# Supplies.net
KiCad netlist of a schematic drawn in Altium Designer
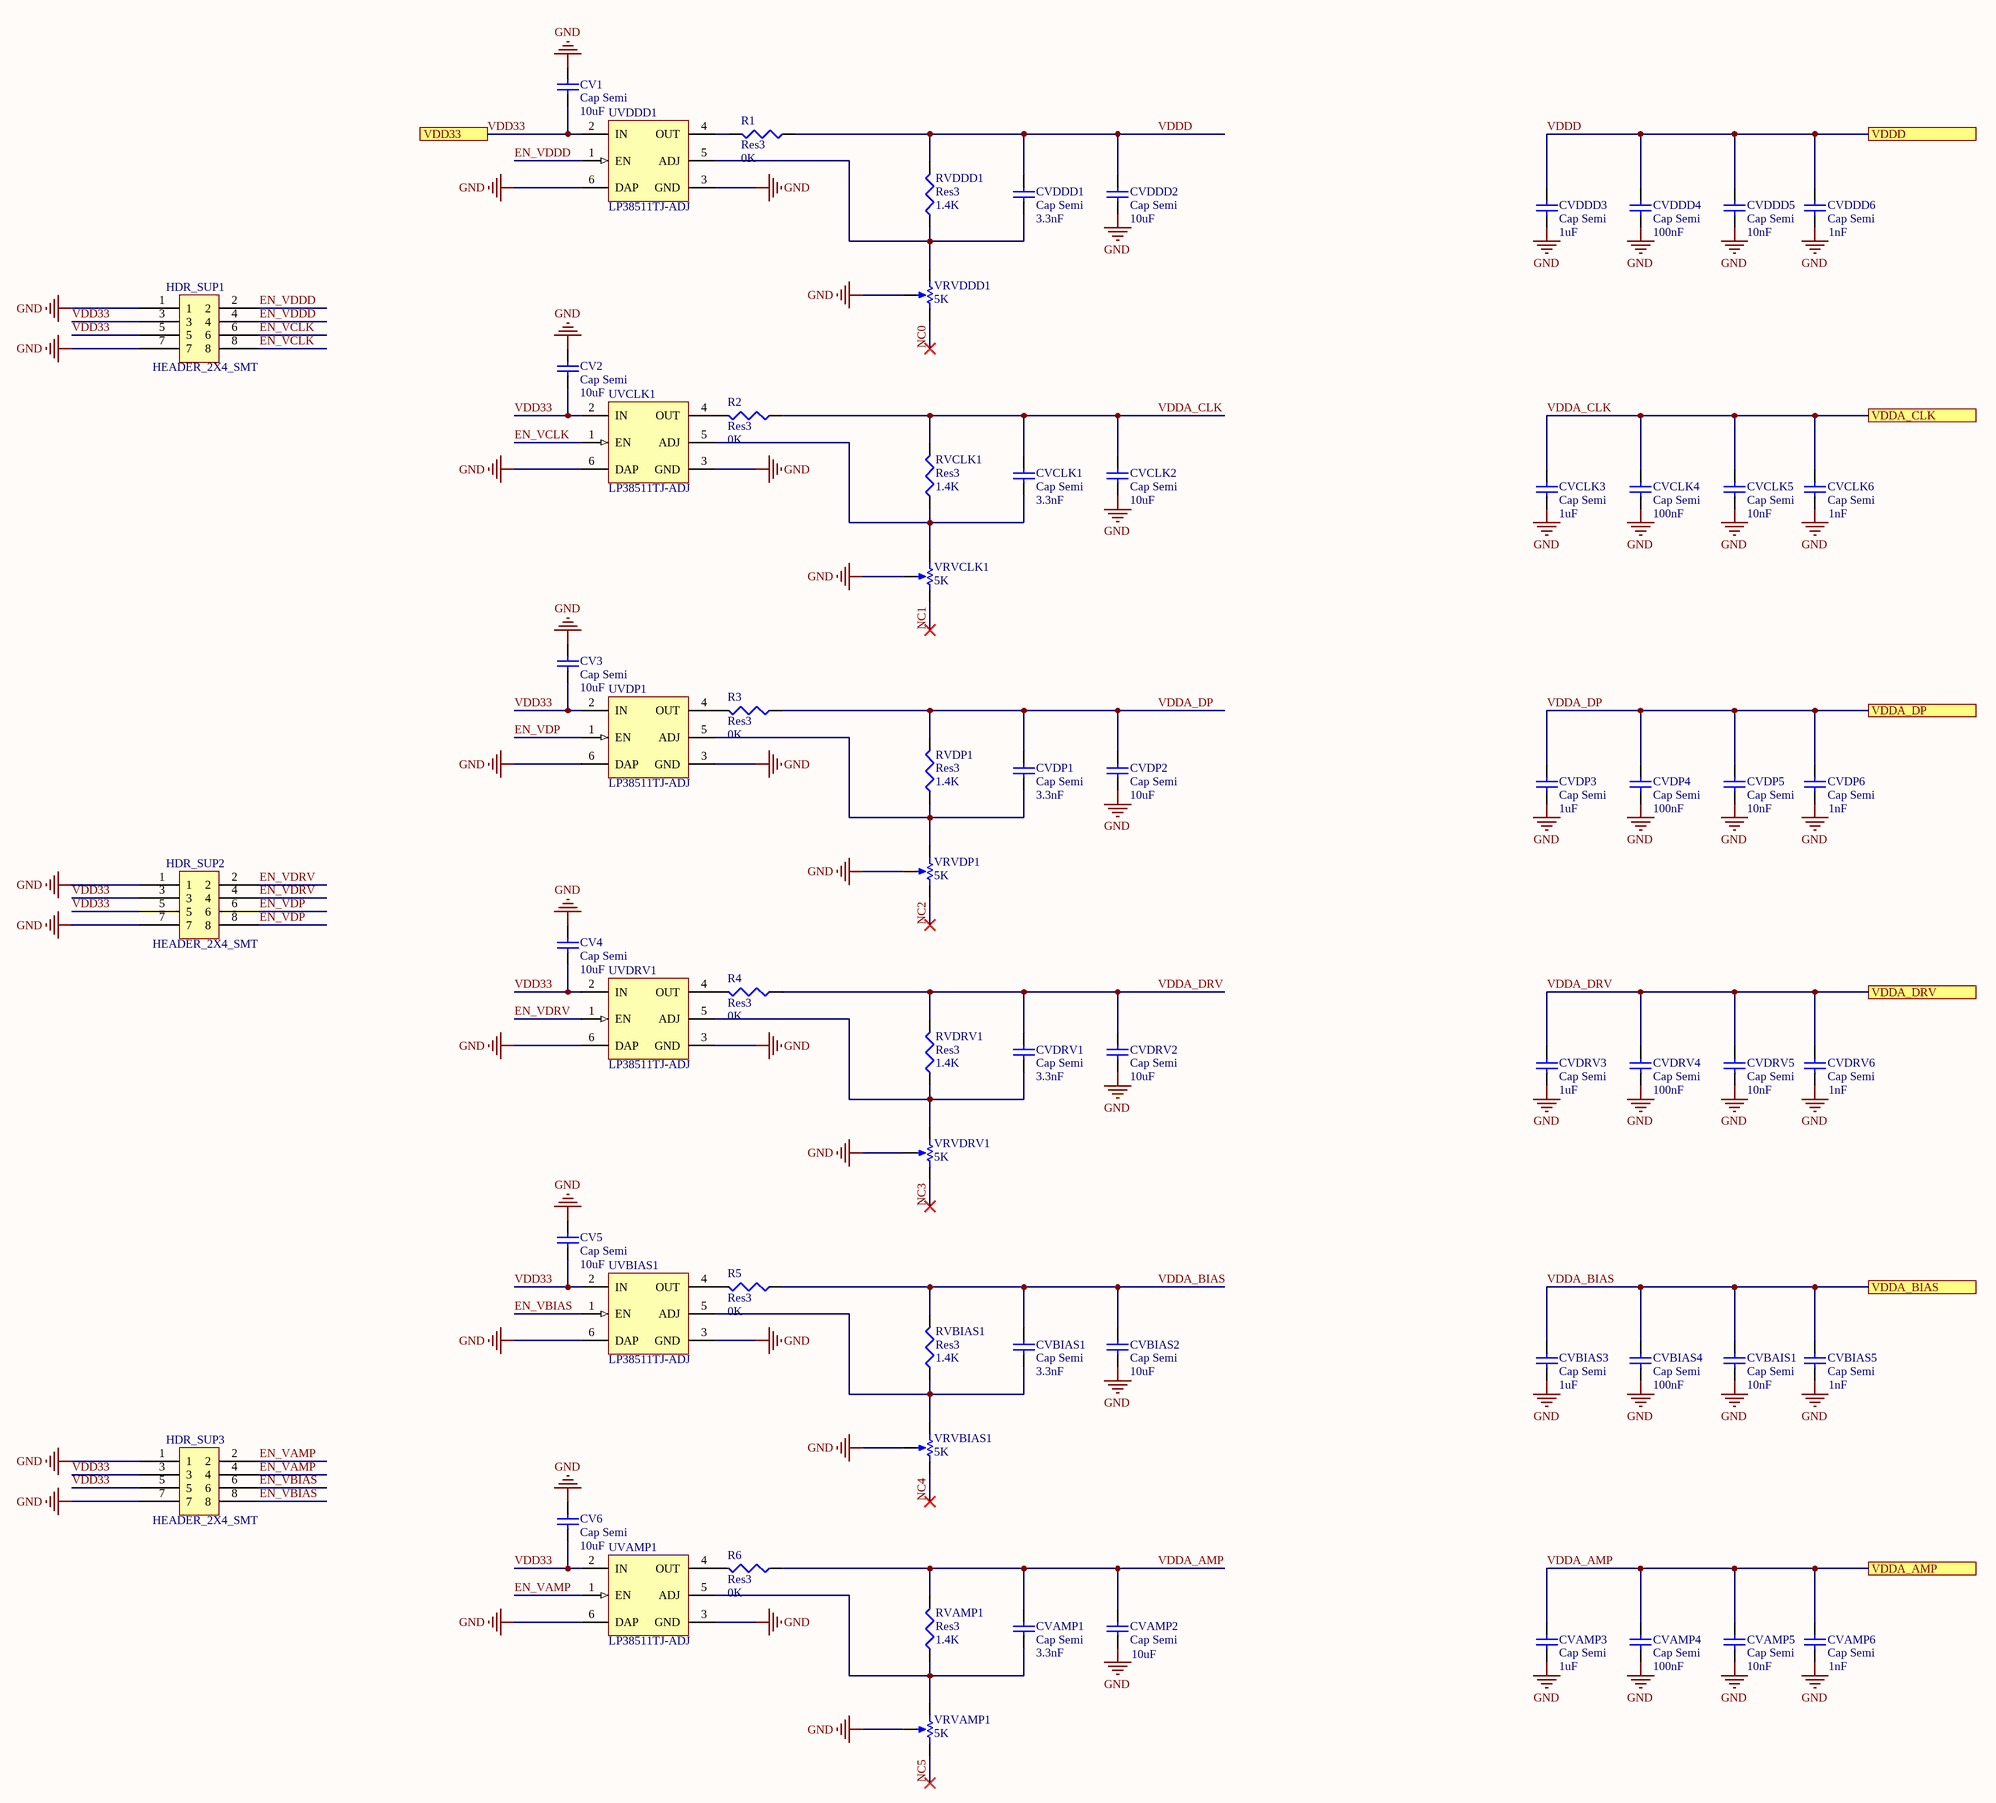
[diagram p0: Supplies.SchDoc]

(export (version "E")
  (design (tool "Eeschema 10.0.6"))
  (components
    (comp (ref "CV1")
      (value "Cap Semi")
      (footprint "1608[0603]")
      (description "Capacitor (Semiconductor SIM Model)")
      (fields (field (name "ALTIUM_VALUE") "10uF") (field (name "PUBLISHER") "Altium Limited"))
      (libsource (lib "Miscellaneous Devices") (part "Cap Semi"))
    )
    (comp (ref "CV2")
      (value "Cap Semi")
      (footprint "1608[0603]")
      (description "Capacitor (Semiconductor SIM Model)")
      (fields (field (name "ALTIUM_VALUE") "10uF") (field (name "PUBLISHER") "Altium Limited"))
      (libsource (lib "Miscellaneous Devices") (part "Cap Semi"))
    )
    (comp (ref "CV3")
      (value "Cap Semi")
      (footprint "1608[0603]")
      (description "Capacitor (Semiconductor SIM Model)")
      (fields (field (name "ALTIUM_VALUE") "10uF") (field (name "PUBLISHER") "Altium Limited"))
      (libsource (lib "Miscellaneous Devices") (part "Cap Semi"))
    )
    (comp (ref "CV4")
      (value "Cap Semi")
      (footprint "1608[0603]")
      (description "Capacitor (Semiconductor SIM Model)")
      (fields (field (name "ALTIUM_VALUE") "10uF") (field (name "PUBLISHER") "Altium Limited"))
      (libsource (lib "Miscellaneous Devices") (part "Cap Semi"))
    )
    (comp (ref "CV5")
      (value "Cap Semi")
      (footprint "1608[0603]")
      (description "Capacitor (Semiconductor SIM Model)")
      (fields (field (name "ALTIUM_VALUE") "10uF") (field (name "PUBLISHER") "Altium Limited"))
      (libsource (lib "Miscellaneous Devices") (part "Cap Semi"))
    )
    (comp (ref "CV6")
      (value "Cap Semi")
      (footprint "1608[0603]")
      (description "Capacitor (Semiconductor SIM Model)")
      (fields (field (name "ALTIUM_VALUE") "10uF") (field (name "PUBLISHER") "Altium Limited"))
      (libsource (lib "Miscellaneous Devices") (part "Cap Semi"))
    )
    (comp (ref "CVAMP1")
      (value "Cap Semi")
      (footprint "1608[0603]")
      (description "Capacitor (Semiconductor SIM Model)")
      (fields (field (name "ALTIUM_VALUE") "3.3nF") (field (name "PUBLISHER") "Altium Limited"))
      (libsource (lib "Miscellaneous Devices") (part "Cap Semi"))
    )
    (comp (ref "CVAMP2")
      (value "Cap Semi")
      (footprint "1608[0603]")
      (description "Capacitor (Semiconductor SIM Model)")
      (fields (field (name "ALTIUM_VALUE") "10uF") (field (name "PUBLISHER") "Altium Limited"))
      (libsource (lib "Miscellaneous Devices") (part "Cap Semi"))
    )
    (comp (ref "CVAMP3")
      (value "Cap Semi")
      (footprint "1608[0603]")
      (description "Capacitor (Semiconductor SIM Model)")
      (fields (field (name "ALTIUM_VALUE") "1uF") (field (name "PUBLISHER") "Altium Limited"))
      (libsource (lib "Miscellaneous Devices") (part "Cap Semi"))
    )
    (comp (ref "CVAMP4")
      (value "Cap Semi")
      (footprint "1608[0603]")
      (description "Capacitor (Semiconductor SIM Model)")
      (fields (field (name "ALTIUM_VALUE") "100nF") (field (name "PUBLISHER") "Altium Limited"))
      (libsource (lib "Miscellaneous Devices") (part "Cap Semi"))
    )
    (comp (ref "CVAMP5")
      (value "Cap Semi")
      (footprint "1608[0603]")
      (description "Capacitor (Semiconductor SIM Model)")
      (fields (field (name "ALTIUM_VALUE") "10nF") (field (name "PUBLISHER") "Altium Limited"))
      (libsource (lib "Miscellaneous Devices") (part "Cap Semi"))
    )
    (comp (ref "CVAMP6")
      (value "Cap Semi")
      (footprint "1608[0603]")
      (description "Capacitor (Semiconductor SIM Model)")
      (fields (field (name "ALTIUM_VALUE") "1nF") (field (name "PUBLISHER") "Altium Limited"))
      (libsource (lib "Miscellaneous Devices") (part "Cap Semi"))
    )
    (comp (ref "CVBAIS1")
      (value "Cap Semi")
      (footprint "1608[0603]")
      (description "Capacitor (Semiconductor SIM Model)")
      (fields (field (name "ALTIUM_VALUE") "10nF") (field (name "PUBLISHER") "Altium Limited"))
      (libsource (lib "Miscellaneous Devices") (part "Cap Semi"))
    )
    (comp (ref "CVBIAS1")
      (value "Cap Semi")
      (footprint "1608[0603]")
      (description "Capacitor (Semiconductor SIM Model)")
      (fields (field (name "ALTIUM_VALUE") "3.3nF") (field (name "PUBLISHER") "Altium Limited"))
      (libsource (lib "Miscellaneous Devices") (part "Cap Semi"))
    )
    (comp (ref "CVBIAS2")
      (value "Cap Semi")
      (footprint "1608[0603]")
      (description "Capacitor (Semiconductor SIM Model)")
      (fields (field (name "ALTIUM_VALUE") "10uF") (field (name "PUBLISHER") "Altium Limited"))
      (libsource (lib "Miscellaneous Devices") (part "Cap Semi"))
    )
    (comp (ref "CVBIAS3")
      (value "Cap Semi")
      (footprint "1608[0603]")
      (description "Capacitor (Semiconductor SIM Model)")
      (fields (field (name "ALTIUM_VALUE") "1uF") (field (name "PUBLISHER") "Altium Limited"))
      (libsource (lib "Miscellaneous Devices") (part "Cap Semi"))
    )
    (comp (ref "CVBIAS4")
      (value "Cap Semi")
      (footprint "1608[0603]")
      (description "Capacitor (Semiconductor SIM Model)")
      (fields (field (name "ALTIUM_VALUE") "100nF") (field (name "PUBLISHER") "Altium Limited"))
      (libsource (lib "Miscellaneous Devices") (part "Cap Semi"))
    )
    (comp (ref "CVBIAS5")
      (value "Cap Semi")
      (footprint "1608[0603]")
      (description "Capacitor (Semiconductor SIM Model)")
      (fields (field (name "ALTIUM_VALUE") "1nF") (field (name "PUBLISHER") "Altium Limited"))
      (libsource (lib "Miscellaneous Devices") (part "Cap Semi"))
    )
    (comp (ref "CVCLK1")
      (value "Cap Semi")
      (footprint "1608[0603]")
      (description "Capacitor (Semiconductor SIM Model)")
      (fields (field (name "ALTIUM_VALUE") "3.3nF") (field (name "PUBLISHER") "Altium Limited"))
      (libsource (lib "Miscellaneous Devices") (part "Cap Semi"))
    )
    (comp (ref "CVCLK2")
      (value "Cap Semi")
      (footprint "1608[0603]")
      (description "Capacitor (Semiconductor SIM Model)")
      (fields (field (name "ALTIUM_VALUE") "10uF") (field (name "PUBLISHER") "Altium Limited"))
      (libsource (lib "Miscellaneous Devices") (part "Cap Semi"))
    )
    (comp (ref "CVCLK3")
      (value "Cap Semi")
      (footprint "1608[0603]")
      (description "Capacitor (Semiconductor SIM Model)")
      (fields (field (name "ALTIUM_VALUE") "1uF") (field (name "PUBLISHER") "Altium Limited"))
      (libsource (lib "Miscellaneous Devices") (part "Cap Semi"))
    )
    (comp (ref "CVCLK4")
      (value "Cap Semi")
      (footprint "1608[0603]")
      (description "Capacitor (Semiconductor SIM Model)")
      (fields (field (name "ALTIUM_VALUE") "100nF") (field (name "PUBLISHER") "Altium Limited"))
      (libsource (lib "Miscellaneous Devices") (part "Cap Semi"))
    )
    (comp (ref "CVCLK5")
      (value "Cap Semi")
      (footprint "1608[0603]")
      (description "Capacitor (Semiconductor SIM Model)")
      (fields (field (name "ALTIUM_VALUE") "10nF") (field (name "PUBLISHER") "Altium Limited"))
      (libsource (lib "Miscellaneous Devices") (part "Cap Semi"))
    )
    (comp (ref "CVCLK6")
      (value "Cap Semi")
      (footprint "1608[0603]")
      (description "Capacitor (Semiconductor SIM Model)")
      (fields (field (name "ALTIUM_VALUE") "1nF") (field (name "PUBLISHER") "Altium Limited"))
      (libsource (lib "Miscellaneous Devices") (part "Cap Semi"))
    )
    (comp (ref "CVDDD1")
      (value "Cap Semi")
      (footprint "1608[0603]")
      (description "Capacitor (Semiconductor SIM Model)")
      (fields (field (name "ALTIUM_VALUE") "3.3nF") (field (name "PUBLISHER") "Altium Limited"))
      (libsource (lib "Miscellaneous Devices") (part "Cap Semi"))
    )
    (comp (ref "CVDDD2")
      (value "Cap Semi")
      (footprint "1608[0603]")
      (description "Capacitor (Semiconductor SIM Model)")
      (fields (field (name "ALTIUM_VALUE") "10uF") (field (name "PUBLISHER") "Altium Limited"))
      (libsource (lib "Miscellaneous Devices") (part "Cap Semi"))
    )
    (comp (ref "CVDDD3")
      (value "Cap Semi")
      (footprint "1608[0603]")
      (description "Capacitor (Semiconductor SIM Model)")
      (fields (field (name "ALTIUM_VALUE") "1uF") (field (name "PUBLISHER") "Altium Limited"))
      (libsource (lib "Miscellaneous Devices") (part "Cap Semi"))
    )
    (comp (ref "CVDDD4")
      (value "Cap Semi")
      (footprint "1608[0603]")
      (description "Capacitor (Semiconductor SIM Model)")
      (fields (field (name "ALTIUM_VALUE") "100nF") (field (name "PUBLISHER") "Altium Limited"))
      (libsource (lib "Miscellaneous Devices") (part "Cap Semi"))
    )
    (comp (ref "CVDDD5")
      (value "Cap Semi")
      (footprint "1608[0603]")
      (description "Capacitor (Semiconductor SIM Model)")
      (fields (field (name "ALTIUM_VALUE") "10nF") (field (name "PUBLISHER") "Altium Limited"))
      (libsource (lib "Miscellaneous Devices") (part "Cap Semi"))
    )
    (comp (ref "CVDDD6")
      (value "Cap Semi")
      (footprint "1608[0603]")
      (description "Capacitor (Semiconductor SIM Model)")
      (fields (field (name "ALTIUM_VALUE") "1nF") (field (name "PUBLISHER") "Altium Limited"))
      (libsource (lib "Miscellaneous Devices") (part "Cap Semi"))
    )
    (comp (ref "CVDP1")
      (value "Cap Semi")
      (footprint "1608[0603]")
      (description "Capacitor (Semiconductor SIM Model)")
      (fields (field (name "ALTIUM_VALUE") "3.3nF") (field (name "PUBLISHER") "Altium Limited"))
      (libsource (lib "Miscellaneous Devices") (part "Cap Semi"))
    )
    (comp (ref "CVDP2")
      (value "Cap Semi")
      (footprint "1608[0603]")
      (description "Capacitor (Semiconductor SIM Model)")
      (fields (field (name "ALTIUM_VALUE") "10uF") (field (name "PUBLISHER") "Altium Limited"))
      (libsource (lib "Miscellaneous Devices") (part "Cap Semi"))
    )
    (comp (ref "CVDP3")
      (value "Cap Semi")
      (footprint "1608[0603]")
      (description "Capacitor (Semiconductor SIM Model)")
      (fields (field (name "ALTIUM_VALUE") "1uF") (field (name "PUBLISHER") "Altium Limited"))
      (libsource (lib "Miscellaneous Devices") (part "Cap Semi"))
    )
    (comp (ref "CVDP4")
      (value "Cap Semi")
      (footprint "1608[0603]")
      (description "Capacitor (Semiconductor SIM Model)")
      (fields (field (name "ALTIUM_VALUE") "100nF") (field (name "PUBLISHER") "Altium Limited"))
      (libsource (lib "Miscellaneous Devices") (part "Cap Semi"))
    )
    (comp (ref "CVDP5")
      (value "Cap Semi")
      (footprint "1608[0603]")
      (description "Capacitor (Semiconductor SIM Model)")
      (fields (field (name "ALTIUM_VALUE") "10nF") (field (name "PUBLISHER") "Altium Limited"))
      (libsource (lib "Miscellaneous Devices") (part "Cap Semi"))
    )
    (comp (ref "CVDP6")
      (value "Cap Semi")
      (footprint "1608[0603]")
      (description "Capacitor (Semiconductor SIM Model)")
      (fields (field (name "ALTIUM_VALUE") "1nF") (field (name "PUBLISHER") "Altium Limited"))
      (libsource (lib "Miscellaneous Devices") (part "Cap Semi"))
    )
    (comp (ref "CVDRV1")
      (value "Cap Semi")
      (footprint "1608[0603]")
      (description "Capacitor (Semiconductor SIM Model)")
      (fields (field (name "ALTIUM_VALUE") "3.3nF") (field (name "PUBLISHER") "Altium Limited"))
      (libsource (lib "Miscellaneous Devices") (part "Cap Semi"))
    )
    (comp (ref "CVDRV2")
      (value "Cap Semi")
      (footprint "1608[0603]")
      (description "Capacitor (Semiconductor SIM Model)")
      (fields (field (name "ALTIUM_VALUE") "10uF") (field (name "PUBLISHER") "Altium Limited"))
      (libsource (lib "Miscellaneous Devices") (part "Cap Semi"))
    )
    (comp (ref "CVDRV3")
      (value "Cap Semi")
      (footprint "1608[0603]")
      (description "Capacitor (Semiconductor SIM Model)")
      (fields (field (name "ALTIUM_VALUE") "1uF") (field (name "PUBLISHER") "Altium Limited"))
      (libsource (lib "Miscellaneous Devices") (part "Cap Semi"))
    )
    (comp (ref "CVDRV4")
      (value "Cap Semi")
      (footprint "1608[0603]")
      (description "Capacitor (Semiconductor SIM Model)")
      (fields (field (name "ALTIUM_VALUE") "100nF") (field (name "PUBLISHER") "Altium Limited"))
      (libsource (lib "Miscellaneous Devices") (part "Cap Semi"))
    )
    (comp (ref "CVDRV5")
      (value "Cap Semi")
      (footprint "1608[0603]")
      (description "Capacitor (Semiconductor SIM Model)")
      (fields (field (name "ALTIUM_VALUE") "10nF") (field (name "PUBLISHER") "Altium Limited"))
      (libsource (lib "Miscellaneous Devices") (part "Cap Semi"))
    )
    (comp (ref "CVDRV6")
      (value "Cap Semi")
      (footprint "1608[0603]")
      (description "Capacitor (Semiconductor SIM Model)")
      (fields (field (name "ALTIUM_VALUE") "1nF") (field (name "PUBLISHER") "Altium Limited"))
      (libsource (lib "Miscellaneous Devices") (part "Cap Semi"))
    )
    (comp (ref "HDR_SUP1")
      (value "HEADER_2X4_SMT")
      (footprint "HEADER_2X4_SMT")
      (libsource (lib "200G_TX_LIB") (part "HEADER_2X4_SMT"))
    )
    (comp (ref "HDR_SUP2")
      (value "HEADER_2X4_SMT")
      (footprint "HEADER_2X4_SMT")
      (libsource (lib "200G_TX_LIB") (part "HEADER_2X4_SMT"))
    )
    (comp (ref "HDR_SUP3")
      (value "HEADER_2X4_SMT")
      (footprint "HEADER_2X4_SMT")
      (libsource (lib "200G_TX_LIB") (part "HEADER_2X4_SMT"))
    )
    (comp (ref "R1")
      (value "Res3")
      (footprint "J1-0603")
      (description "Resistor")
      (fields (field (name "ALTIUM_VALUE") "0K") (field (name "PUBLISHER") "Altium Limited"))
      (libsource (lib "Miscellaneous Devices") (part "Res3"))
    )
    (comp (ref "R2")
      (value "Res3")
      (footprint "J1-0603")
      (description "Resistor")
      (fields (field (name "ALTIUM_VALUE") "0K") (field (name "PUBLISHER") "Altium Limited"))
      (libsource (lib "Miscellaneous Devices") (part "Res3"))
    )
    (comp (ref "R3")
      (value "Res3")
      (footprint "J1-0603")
      (description "Resistor")
      (fields (field (name "ALTIUM_VALUE") "0K") (field (name "PUBLISHER") "Altium Limited"))
      (libsource (lib "Miscellaneous Devices") (part "Res3"))
    )
    (comp (ref "R4")
      (value "Res3")
      (footprint "J1-0603")
      (description "Resistor")
      (fields (field (name "ALTIUM_VALUE") "0K") (field (name "PUBLISHER") "Altium Limited"))
      (libsource (lib "Miscellaneous Devices") (part "Res3"))
    )
    (comp (ref "R5")
      (value "Res3")
      (footprint "J1-0603")
      (description "Resistor")
      (fields (field (name "ALTIUM_VALUE") "0K") (field (name "PUBLISHER") "Altium Limited"))
      (libsource (lib "Miscellaneous Devices") (part "Res3"))
    )
    (comp (ref "R6")
      (value "Res3")
      (footprint "J1-0603")
      (description "Resistor")
      (fields (field (name "ALTIUM_VALUE") "0K") (field (name "PUBLISHER") "Altium Limited"))
      (libsource (lib "Miscellaneous Devices") (part "Res3"))
    )
    (comp (ref "RVAMP1")
      (value "Res3")
      (footprint "J1-0603")
      (description "Resistor")
      (fields (field (name "ALTIUM_VALUE") "1.4K") (field (name "PUBLISHER") "Altium Limited"))
      (libsource (lib "Miscellaneous Devices") (part "Res3"))
    )
    (comp (ref "RVBIAS1")
      (value "Res3")
      (footprint "J1-0603")
      (description "Resistor")
      (fields (field (name "ALTIUM_VALUE") "1.4K") (field (name "PUBLISHER") "Altium Limited"))
      (libsource (lib "Miscellaneous Devices") (part "Res3"))
    )
    (comp (ref "RVCLK1")
      (value "Res3")
      (footprint "J1-0603")
      (description "Resistor")
      (fields (field (name "ALTIUM_VALUE") "1.4K") (field (name "PUBLISHER") "Altium Limited"))
      (libsource (lib "Miscellaneous Devices") (part "Res3"))
    )
    (comp (ref "RVDDD1")
      (value "Res3")
      (footprint "J1-0603")
      (description "Resistor")
      (fields (field (name "ALTIUM_VALUE") "1.4K") (field (name "PUBLISHER") "Altium Limited"))
      (libsource (lib "Miscellaneous Devices") (part "Res3"))
    )
    (comp (ref "RVDP1")
      (value "Res3")
      (footprint "J1-0603")
      (description "Resistor")
      (fields (field (name "ALTIUM_VALUE") "1.4K") (field (name "PUBLISHER") "Altium Limited"))
      (libsource (lib "Miscellaneous Devices") (part "Res3"))
    )
    (comp (ref "RVDRV1")
      (value "Res3")
      (footprint "J1-0603")
      (description "Resistor")
      (fields (field (name "ALTIUM_VALUE") "1.4K") (field (name "PUBLISHER") "Altium Limited"))
      (libsource (lib "Miscellaneous Devices") (part "Res3"))
    )
    (comp (ref "UVAMP1")
      (value "LP38511TJ-ADJ")
      (footprint "TJ5A_N")
      (fields (field (name "MANUFACTURER") "National Semiconductor"))
      (libsource (lib "National Semiconductor LDO") (part "LP38511TJ-ADJ"))
    )
    (comp (ref "UVBIAS1")
      (value "LP38511TJ-ADJ")
      (footprint "TJ5A_N")
      (fields (field (name "MANUFACTURER") "National Semiconductor"))
      (libsource (lib "National Semiconductor LDO") (part "LP38511TJ-ADJ"))
    )
    (comp (ref "UVCLK1")
      (value "LP38511TJ-ADJ")
      (footprint "TJ5A_N")
      (fields (field (name "MANUFACTURER") "National Semiconductor"))
      (libsource (lib "National Semiconductor LDO") (part "LP38511TJ-ADJ"))
    )
    (comp (ref "UVDDD1")
      (value "LP38511TJ-ADJ")
      (footprint "TJ5A_N")
      (fields (field (name "MANUFACTURER") "National Semiconductor"))
      (libsource (lib "National Semiconductor LDO") (part "LP38511TJ-ADJ"))
    )
    (comp (ref "UVDP1")
      (value "LP38511TJ-ADJ")
      (footprint "TJ5A_N")
      (fields (field (name "MANUFACTURER") "National Semiconductor"))
      (libsource (lib "National Semiconductor LDO") (part "LP38511TJ-ADJ"))
    )
    (comp (ref "UVDRV1")
      (value "LP38511TJ-ADJ")
      (footprint "TJ5A_N")
      (fields (field (name "MANUFACTURER") "National Semiconductor"))
      (libsource (lib "National Semiconductor LDO") (part "LP38511TJ-ADJ"))
    )
    (comp (ref "VRVAMP1")
      (value "5K")
      (footprint "POT_3214_Top")
      (description "Potentiometer")
      (fields (field (name "MANUFACTURER") "Bourns"))
      (libsource (lib "Jaeduk_Library") (part "RPot_5K"))
    )
    (comp (ref "VRVBIAS1")
      (value "5K")
      (footprint "POT_3214_Top")
      (description "Potentiometer")
      (fields (field (name "MANUFACTURER") "Bourns"))
      (libsource (lib "Jaeduk_Library") (part "RPot_5K"))
    )
    (comp (ref "VRVCLK1")
      (value "5K")
      (footprint "POT_3214_Top")
      (description "Potentiometer")
      (fields (field (name "MANUFACTURER") "Bourns"))
      (libsource (lib "Jaeduk_Library") (part "RPot_5K"))
    )
    (comp (ref "VRVDDD1")
      (value "5K")
      (footprint "POT_3214_Top")
      (description "Potentiometer")
      (fields (field (name "MANUFACTURER") "Bourns"))
      (libsource (lib "Jaeduk_Library") (part "RPot_5K"))
    )
    (comp (ref "VRVDP1")
      (value "5K")
      (footprint "POT_3214_Top")
      (description "Potentiometer")
      (fields (field (name "MANUFACTURER") "Bourns"))
      (libsource (lib "Jaeduk_Library") (part "RPot_5K"))
    )
    (comp (ref "VRVDRV1")
      (value "5K")
      (footprint "POT_3214_Top")
      (description "Potentiometer")
      (fields (field (name "MANUFACTURER") "Bourns"))
      (libsource (lib "Jaeduk_Library") (part "RPot_5K"))
    )
  )
  (nets
    (net (code "1") (name "/EN_VAMP") (class "Default")
      (node (ref "HDR_SUP3") (pin "2") (pinfunction "2_2") (pintype "passive"))
      (node (ref "HDR_SUP3") (pin "4") (pinfunction "4_4") (pintype "passive"))
      (node (ref "UVAMP1") (pin "1") (pinfunction "EN_1") (pintype "input"))
    )
    (net (code "2") (name "/EN_VBIAS") (class "Default")
      (node (ref "HDR_SUP3") (pin "6") (pinfunction "6_6") (pintype "passive"))
      (node (ref "HDR_SUP3") (pin "8") (pinfunction "8_8") (pintype "passive"))
      (node (ref "UVBIAS1") (pin "1") (pinfunction "EN_1") (pintype "input"))
    )
    (net (code "3") (name "/EN_VCLK") (class "Default")
      (node (ref "HDR_SUP1") (pin "6") (pinfunction "6_6") (pintype "passive"))
      (node (ref "HDR_SUP1") (pin "8") (pinfunction "8_8") (pintype "passive"))
      (node (ref "UVCLK1") (pin "1") (pinfunction "EN_1") (pintype "input"))
    )
    (net (code "4") (name "/EN_VDDD") (class "Default")
      (node (ref "HDR_SUP1") (pin "2") (pinfunction "2_2") (pintype "passive"))
      (node (ref "HDR_SUP1") (pin "4") (pinfunction "4_4") (pintype "passive"))
      (node (ref "UVDDD1") (pin "1") (pinfunction "EN_1") (pintype "input"))
    )
    (net (code "5") (name "/EN_VDP") (class "Default")
      (node (ref "HDR_SUP2") (pin "6") (pinfunction "6_6") (pintype "passive"))
      (node (ref "HDR_SUP2") (pin "8") (pinfunction "8_8") (pintype "passive"))
      (node (ref "UVDP1") (pin "1") (pinfunction "EN_1") (pintype "input"))
    )
    (net (code "6") (name "/EN_VDRV") (class "Default")
      (node (ref "HDR_SUP2") (pin "2") (pinfunction "2_2") (pintype "passive"))
      (node (ref "HDR_SUP2") (pin "4") (pinfunction "4_4") (pintype "passive"))
      (node (ref "UVDRV1") (pin "1") (pinfunction "EN_1") (pintype "input"))
    )
    (net (code "7") (name "/NC0") (class "Default")
      (node (ref "VRVDDD1") (pin "3") (pinfunction "BOT_3") (pintype "passive+no_connect"))
    )
    (net (code "8") (name "/NC1") (class "Default")
      (node (ref "VRVCLK1") (pin "3") (pinfunction "BOT_3") (pintype "passive+no_connect"))
    )
    (net (code "9") (name "/NC2") (class "Default")
      (node (ref "VRVDP1") (pin "3") (pinfunction "BOT_3") (pintype "passive+no_connect"))
    )
    (net (code "10") (name "/NC3") (class "Default")
      (node (ref "VRVDRV1") (pin "3") (pinfunction "BOT_3") (pintype "passive+no_connect"))
    )
    (net (code "11") (name "/NC4") (class "Default")
      (node (ref "VRVBIAS1") (pin "3") (pinfunction "BOT_3") (pintype "passive+no_connect"))
    )
    (net (code "12") (name "/NC5") (class "Default")
      (node (ref "VRVAMP1") (pin "3") (pinfunction "BOT_3") (pintype "passive+no_connect"))
    )
    (net (code "13") (name "/VDD33") (class "Default")
      (node (ref "CV1") (pin "2") (pinfunction "2_2") (pintype "passive"))
      (node (ref "CV2") (pin "2") (pinfunction "2_2") (pintype "passive"))
      (node (ref "CV3") (pin "2") (pinfunction "2_2") (pintype "passive"))
      (node (ref "CV4") (pin "2") (pinfunction "2_2") (pintype "passive"))
      (node (ref "CV5") (pin "2") (pinfunction "2_2") (pintype "passive"))
      (node (ref "CV6") (pin "2") (pinfunction "2_2") (pintype "passive"))
      (node (ref "HDR_SUP1") (pin "3") (pinfunction "3_3") (pintype "passive"))
      (node (ref "HDR_SUP1") (pin "5") (pinfunction "5_5") (pintype "passive"))
      (node (ref "HDR_SUP2") (pin "3") (pinfunction "3_3") (pintype "passive"))
      (node (ref "HDR_SUP2") (pin "5") (pinfunction "5_5") (pintype "passive"))
      (node (ref "HDR_SUP3") (pin "3") (pinfunction "3_3") (pintype "passive"))
      (node (ref "HDR_SUP3") (pin "5") (pinfunction "5_5") (pintype "passive"))
      (node (ref "UVAMP1") (pin "2") (pinfunction "IN_2") (pintype "power_in"))
      (node (ref "UVBIAS1") (pin "2") (pinfunction "IN_2") (pintype "power_in"))
      (node (ref "UVCLK1") (pin "2") (pinfunction "IN_2") (pintype "power_in"))
      (node (ref "UVDDD1") (pin "2") (pinfunction "IN_2") (pintype "power_in"))
      (node (ref "UVDP1") (pin "2") (pinfunction "IN_2") (pintype "power_in"))
      (node (ref "UVDRV1") (pin "2") (pinfunction "IN_2") (pintype "power_in"))
    )
    (net (code "14") (name "/VDDA_AMP") (class "Default")
      (node (ref "CVAMP1") (pin "2") (pinfunction "2_2") (pintype "passive"))
      (node (ref "CVAMP2") (pin "2") (pinfunction "2_2") (pintype "passive"))
      (node (ref "CVAMP3") (pin "2") (pinfunction "2_2") (pintype "passive"))
      (node (ref "CVAMP4") (pin "2") (pinfunction "2_2") (pintype "passive"))
      (node (ref "CVAMP5") (pin "2") (pinfunction "2_2") (pintype "passive"))
      (node (ref "CVAMP6") (pin "2") (pinfunction "2_2") (pintype "passive"))
      (node (ref "R6") (pin "1") (pinfunction "1_1") (pintype "passive"))
      (node (ref "RVAMP1") (pin "2") (pinfunction "2_2") (pintype "passive"))
    )
    (net (code "15") (name "/VDDA_BIAS") (class "Default")
      (node (ref "CVBAIS1") (pin "2") (pinfunction "2_2") (pintype "passive"))
      (node (ref "CVBIAS1") (pin "2") (pinfunction "2_2") (pintype "passive"))
      (node (ref "CVBIAS2") (pin "2") (pinfunction "2_2") (pintype "passive"))
      (node (ref "CVBIAS3") (pin "2") (pinfunction "2_2") (pintype "passive"))
      (node (ref "CVBIAS4") (pin "2") (pinfunction "2_2") (pintype "passive"))
      (node (ref "CVBIAS5") (pin "2") (pinfunction "2_2") (pintype "passive"))
      (node (ref "R5") (pin "1") (pinfunction "1_1") (pintype "passive"))
      (node (ref "RVBIAS1") (pin "2") (pinfunction "2_2") (pintype "passive"))
    )
    (net (code "16") (name "/VDDA_CLK") (class "Default")
      (node (ref "CVCLK1") (pin "2") (pinfunction "2_2") (pintype "passive"))
      (node (ref "CVCLK2") (pin "2") (pinfunction "2_2") (pintype "passive"))
      (node (ref "CVCLK3") (pin "2") (pinfunction "2_2") (pintype "passive"))
      (node (ref "CVCLK4") (pin "2") (pinfunction "2_2") (pintype "passive"))
      (node (ref "CVCLK5") (pin "2") (pinfunction "2_2") (pintype "passive"))
      (node (ref "CVCLK6") (pin "2") (pinfunction "2_2") (pintype "passive"))
      (node (ref "R2") (pin "1") (pinfunction "1_1") (pintype "passive"))
      (node (ref "RVCLK1") (pin "2") (pinfunction "2_2") (pintype "passive"))
    )
    (net (code "17") (name "/VDDA_DP") (class "Default")
      (node (ref "CVDP1") (pin "2") (pinfunction "2_2") (pintype "passive"))
      (node (ref "CVDP2") (pin "2") (pinfunction "2_2") (pintype "passive"))
      (node (ref "CVDP3") (pin "2") (pinfunction "2_2") (pintype "passive"))
      (node (ref "CVDP4") (pin "2") (pinfunction "2_2") (pintype "passive"))
      (node (ref "CVDP5") (pin "2") (pinfunction "2_2") (pintype "passive"))
      (node (ref "CVDP6") (pin "2") (pinfunction "2_2") (pintype "passive"))
      (node (ref "R3") (pin "1") (pinfunction "1_1") (pintype "passive"))
      (node (ref "RVDP1") (pin "2") (pinfunction "2_2") (pintype "passive"))
    )
    (net (code "18") (name "/VDDA_DRV") (class "Default")
      (node (ref "CVDRV1") (pin "2") (pinfunction "2_2") (pintype "passive"))
      (node (ref "CVDRV2") (pin "2") (pinfunction "2_2") (pintype "passive"))
      (node (ref "CVDRV3") (pin "2") (pinfunction "2_2") (pintype "passive"))
      (node (ref "CVDRV4") (pin "2") (pinfunction "2_2") (pintype "passive"))
      (node (ref "CVDRV5") (pin "2") (pinfunction "2_2") (pintype "passive"))
      (node (ref "CVDRV6") (pin "2") (pinfunction "2_2") (pintype "passive"))
      (node (ref "R4") (pin "1") (pinfunction "1_1") (pintype "passive"))
      (node (ref "RVDRV1") (pin "2") (pinfunction "2_2") (pintype "passive"))
    )
    (net (code "19") (name "/VDDD") (class "Default")
      (node (ref "CVDDD1") (pin "2") (pinfunction "2_2") (pintype "passive"))
      (node (ref "CVDDD2") (pin "2") (pinfunction "2_2") (pintype "passive"))
      (node (ref "CVDDD3") (pin "2") (pinfunction "2_2") (pintype "passive"))
      (node (ref "CVDDD4") (pin "2") (pinfunction "2_2") (pintype "passive"))
      (node (ref "CVDDD5") (pin "2") (pinfunction "2_2") (pintype "passive"))
      (node (ref "CVDDD6") (pin "2") (pinfunction "2_2") (pintype "passive"))
      (node (ref "R1") (pin "1") (pinfunction "1_1") (pintype "passive"))
      (node (ref "RVDDD1") (pin "2") (pinfunction "2_2") (pintype "passive"))
    )
    (net (code "20") (name "GND") (class "Default")
      (node (ref "CV1") (pin "1") (pinfunction "1_1") (pintype "passive"))
      (node (ref "CV2") (pin "1") (pinfunction "1_1") (pintype "passive"))
      (node (ref "CV3") (pin "1") (pinfunction "1_1") (pintype "passive"))
      (node (ref "CV4") (pin "1") (pinfunction "1_1") (pintype "passive"))
      (node (ref "CV5") (pin "1") (pinfunction "1_1") (pintype "passive"))
      (node (ref "CV6") (pin "1") (pinfunction "1_1") (pintype "passive"))
      (node (ref "CVAMP2") (pin "1") (pinfunction "1_1") (pintype "passive"))
      (node (ref "CVAMP3") (pin "1") (pinfunction "1_1") (pintype "passive"))
      (node (ref "CVAMP4") (pin "1") (pinfunction "1_1") (pintype "passive"))
      (node (ref "CVAMP5") (pin "1") (pinfunction "1_1") (pintype "passive"))
      (node (ref "CVAMP6") (pin "1") (pinfunction "1_1") (pintype "passive"))
      (node (ref "CVBAIS1") (pin "1") (pinfunction "1_1") (pintype "passive"))
      (node (ref "CVBIAS2") (pin "1") (pinfunction "1_1") (pintype "passive"))
      (node (ref "CVBIAS3") (pin "1") (pinfunction "1_1") (pintype "passive"))
      (node (ref "CVBIAS4") (pin "1") (pinfunction "1_1") (pintype "passive"))
      (node (ref "CVBIAS5") (pin "1") (pinfunction "1_1") (pintype "passive"))
      (node (ref "CVCLK2") (pin "1") (pinfunction "1_1") (pintype "passive"))
      (node (ref "CVCLK3") (pin "1") (pinfunction "1_1") (pintype "passive"))
      (node (ref "CVCLK4") (pin "1") (pinfunction "1_1") (pintype "passive"))
      (node (ref "CVCLK5") (pin "1") (pinfunction "1_1") (pintype "passive"))
      (node (ref "CVCLK6") (pin "1") (pinfunction "1_1") (pintype "passive"))
      (node (ref "CVDDD2") (pin "1") (pinfunction "1_1") (pintype "passive"))
      (node (ref "CVDDD3") (pin "1") (pinfunction "1_1") (pintype "passive"))
      (node (ref "CVDDD4") (pin "1") (pinfunction "1_1") (pintype "passive"))
      (node (ref "CVDDD5") (pin "1") (pinfunction "1_1") (pintype "passive"))
      (node (ref "CVDDD6") (pin "1") (pinfunction "1_1") (pintype "passive"))
      (node (ref "CVDP2") (pin "1") (pinfunction "1_1") (pintype "passive"))
      (node (ref "CVDP3") (pin "1") (pinfunction "1_1") (pintype "passive"))
      (node (ref "CVDP4") (pin "1") (pinfunction "1_1") (pintype "passive"))
      (node (ref "CVDP5") (pin "1") (pinfunction "1_1") (pintype "passive"))
      (node (ref "CVDP6") (pin "1") (pinfunction "1_1") (pintype "passive"))
      (node (ref "CVDRV2") (pin "1") (pinfunction "1_1") (pintype "passive"))
      (node (ref "CVDRV3") (pin "1") (pinfunction "1_1") (pintype "passive"))
      (node (ref "CVDRV4") (pin "1") (pinfunction "1_1") (pintype "passive"))
      (node (ref "CVDRV5") (pin "1") (pinfunction "1_1") (pintype "passive"))
      (node (ref "CVDRV6") (pin "1") (pinfunction "1_1") (pintype "passive"))
      (node (ref "HDR_SUP1") (pin "1") (pinfunction "1_1") (pintype "passive"))
      (node (ref "HDR_SUP1") (pin "7") (pinfunction "7_7") (pintype "passive"))
      (node (ref "HDR_SUP2") (pin "1") (pinfunction "1_1") (pintype "passive"))
      (node (ref "HDR_SUP2") (pin "7") (pinfunction "7_7") (pintype "passive"))
      (node (ref "HDR_SUP3") (pin "1") (pinfunction "1_1") (pintype "passive"))
      (node (ref "HDR_SUP3") (pin "7") (pinfunction "7_7") (pintype "passive"))
      (node (ref "UVAMP1") (pin "3") (pinfunction "GND_3") (pintype "power_in"))
      (node (ref "UVAMP1") (pin "6") (pinfunction "DAP_6") (pintype "power_in"))
      (node (ref "UVBIAS1") (pin "3") (pinfunction "GND_3") (pintype "power_in"))
      (node (ref "UVBIAS1") (pin "6") (pinfunction "DAP_6") (pintype "power_in"))
      (node (ref "UVCLK1") (pin "3") (pinfunction "GND_3") (pintype "power_in"))
      (node (ref "UVCLK1") (pin "6") (pinfunction "DAP_6") (pintype "power_in"))
      (node (ref "UVDDD1") (pin "3") (pinfunction "GND_3") (pintype "power_in"))
      (node (ref "UVDDD1") (pin "6") (pinfunction "DAP_6") (pintype "power_in"))
      (node (ref "UVDP1") (pin "3") (pinfunction "GND_3") (pintype "power_in"))
      (node (ref "UVDP1") (pin "6") (pinfunction "DAP_6") (pintype "power_in"))
      (node (ref "UVDRV1") (pin "3") (pinfunction "GND_3") (pintype "power_in"))
      (node (ref "UVDRV1") (pin "6") (pinfunction "DAP_6") (pintype "power_in"))
      (node (ref "VRVAMP1") (pin "2") (pinfunction "TAP_2") (pintype "passive"))
      (node (ref "VRVBIAS1") (pin "2") (pinfunction "TAP_2") (pintype "passive"))
      (node (ref "VRVCLK1") (pin "2") (pinfunction "TAP_2") (pintype "passive"))
      (node (ref "VRVDDD1") (pin "2") (pinfunction "TAP_2") (pintype "passive"))
      (node (ref "VRVDP1") (pin "2") (pinfunction "TAP_2") (pintype "passive"))
      (node (ref "VRVDRV1") (pin "2") (pinfunction "TAP_2") (pintype "passive"))
    )
    (net (code "21") (name "Net-(UVAMP1-ADJ)") (class "Default")
      (node (ref "CVAMP1") (pin "1") (pinfunction "1_1") (pintype "passive"))
      (node (ref "RVAMP1") (pin "1") (pinfunction "1_1") (pintype "passive"))
      (node (ref "UVAMP1") (pin "5") (pinfunction "ADJ_5") (pintype "passive"))
      (node (ref "VRVAMP1") (pin "1") (pinfunction "TOP_1") (pintype "passive"))
    )
    (net (code "22") (name "Net-(UVAMP1-OUT)") (class "Default")
      (node (ref "R6") (pin "2") (pinfunction "2_2") (pintype "passive"))
      (node (ref "UVAMP1") (pin "4") (pinfunction "OUT_4") (pintype "power_in"))
    )
    (net (code "23") (name "Net-(UVBIAS1-ADJ)") (class "Default")
      (node (ref "CVBIAS1") (pin "1") (pinfunction "1_1") (pintype "passive"))
      (node (ref "RVBIAS1") (pin "1") (pinfunction "1_1") (pintype "passive"))
      (node (ref "UVBIAS1") (pin "5") (pinfunction "ADJ_5") (pintype "passive"))
      (node (ref "VRVBIAS1") (pin "1") (pinfunction "TOP_1") (pintype "passive"))
    )
    (net (code "24") (name "Net-(UVBIAS1-OUT)") (class "Default")
      (node (ref "R5") (pin "2") (pinfunction "2_2") (pintype "passive"))
      (node (ref "UVBIAS1") (pin "4") (pinfunction "OUT_4") (pintype "power_in"))
    )
    (net (code "25") (name "Net-(UVCLK1-ADJ)") (class "Default")
      (node (ref "CVCLK1") (pin "1") (pinfunction "1_1") (pintype "passive"))
      (node (ref "RVCLK1") (pin "1") (pinfunction "1_1") (pintype "passive"))
      (node (ref "UVCLK1") (pin "5") (pinfunction "ADJ_5") (pintype "passive"))
      (node (ref "VRVCLK1") (pin "1") (pinfunction "TOP_1") (pintype "passive"))
    )
    (net (code "26") (name "Net-(UVCLK1-OUT)") (class "Default")
      (node (ref "R2") (pin "2") (pinfunction "2_2") (pintype "passive"))
      (node (ref "UVCLK1") (pin "4") (pinfunction "OUT_4") (pintype "power_in"))
    )
    (net (code "27") (name "Net-(UVDDD1-ADJ)") (class "Default")
      (node (ref "CVDDD1") (pin "1") (pinfunction "1_1") (pintype "passive"))
      (node (ref "RVDDD1") (pin "1") (pinfunction "1_1") (pintype "passive"))
      (node (ref "UVDDD1") (pin "5") (pinfunction "ADJ_5") (pintype "passive"))
      (node (ref "VRVDDD1") (pin "1") (pinfunction "TOP_1") (pintype "passive"))
    )
    (net (code "28") (name "Net-(UVDDD1-OUT)") (class "Default")
      (node (ref "R1") (pin "2") (pinfunction "2_2") (pintype "passive"))
      (node (ref "UVDDD1") (pin "4") (pinfunction "OUT_4") (pintype "power_in"))
    )
    (net (code "29") (name "Net-(UVDP1-ADJ)") (class "Default")
      (node (ref "CVDP1") (pin "1") (pinfunction "1_1") (pintype "passive"))
      (node (ref "RVDP1") (pin "1") (pinfunction "1_1") (pintype "passive"))
      (node (ref "UVDP1") (pin "5") (pinfunction "ADJ_5") (pintype "passive"))
      (node (ref "VRVDP1") (pin "1") (pinfunction "TOP_1") (pintype "passive"))
    )
    (net (code "30") (name "Net-(UVDP1-OUT)") (class "Default")
      (node (ref "R3") (pin "2") (pinfunction "2_2") (pintype "passive"))
      (node (ref "UVDP1") (pin "4") (pinfunction "OUT_4") (pintype "power_in"))
    )
    (net (code "31") (name "Net-(UVDRV1-ADJ)") (class "Default")
      (node (ref "CVDRV1") (pin "1") (pinfunction "1_1") (pintype "passive"))
      (node (ref "RVDRV1") (pin "1") (pinfunction "1_1") (pintype "passive"))
      (node (ref "UVDRV1") (pin "5") (pinfunction "ADJ_5") (pintype "passive"))
      (node (ref "VRVDRV1") (pin "1") (pinfunction "TOP_1") (pintype "passive"))
    )
    (net (code "32") (name "Net-(UVDRV1-OUT)") (class "Default")
      (node (ref "R4") (pin "2") (pinfunction "2_2") (pintype "passive"))
      (node (ref "UVDRV1") (pin "4") (pinfunction "OUT_4") (pintype "power_in"))
    )
  )
)
